# LB_BIT_1IN_2OUT-XL-v03_1_1x.net
KiCad netlist of a schematic drawn in EAGLE
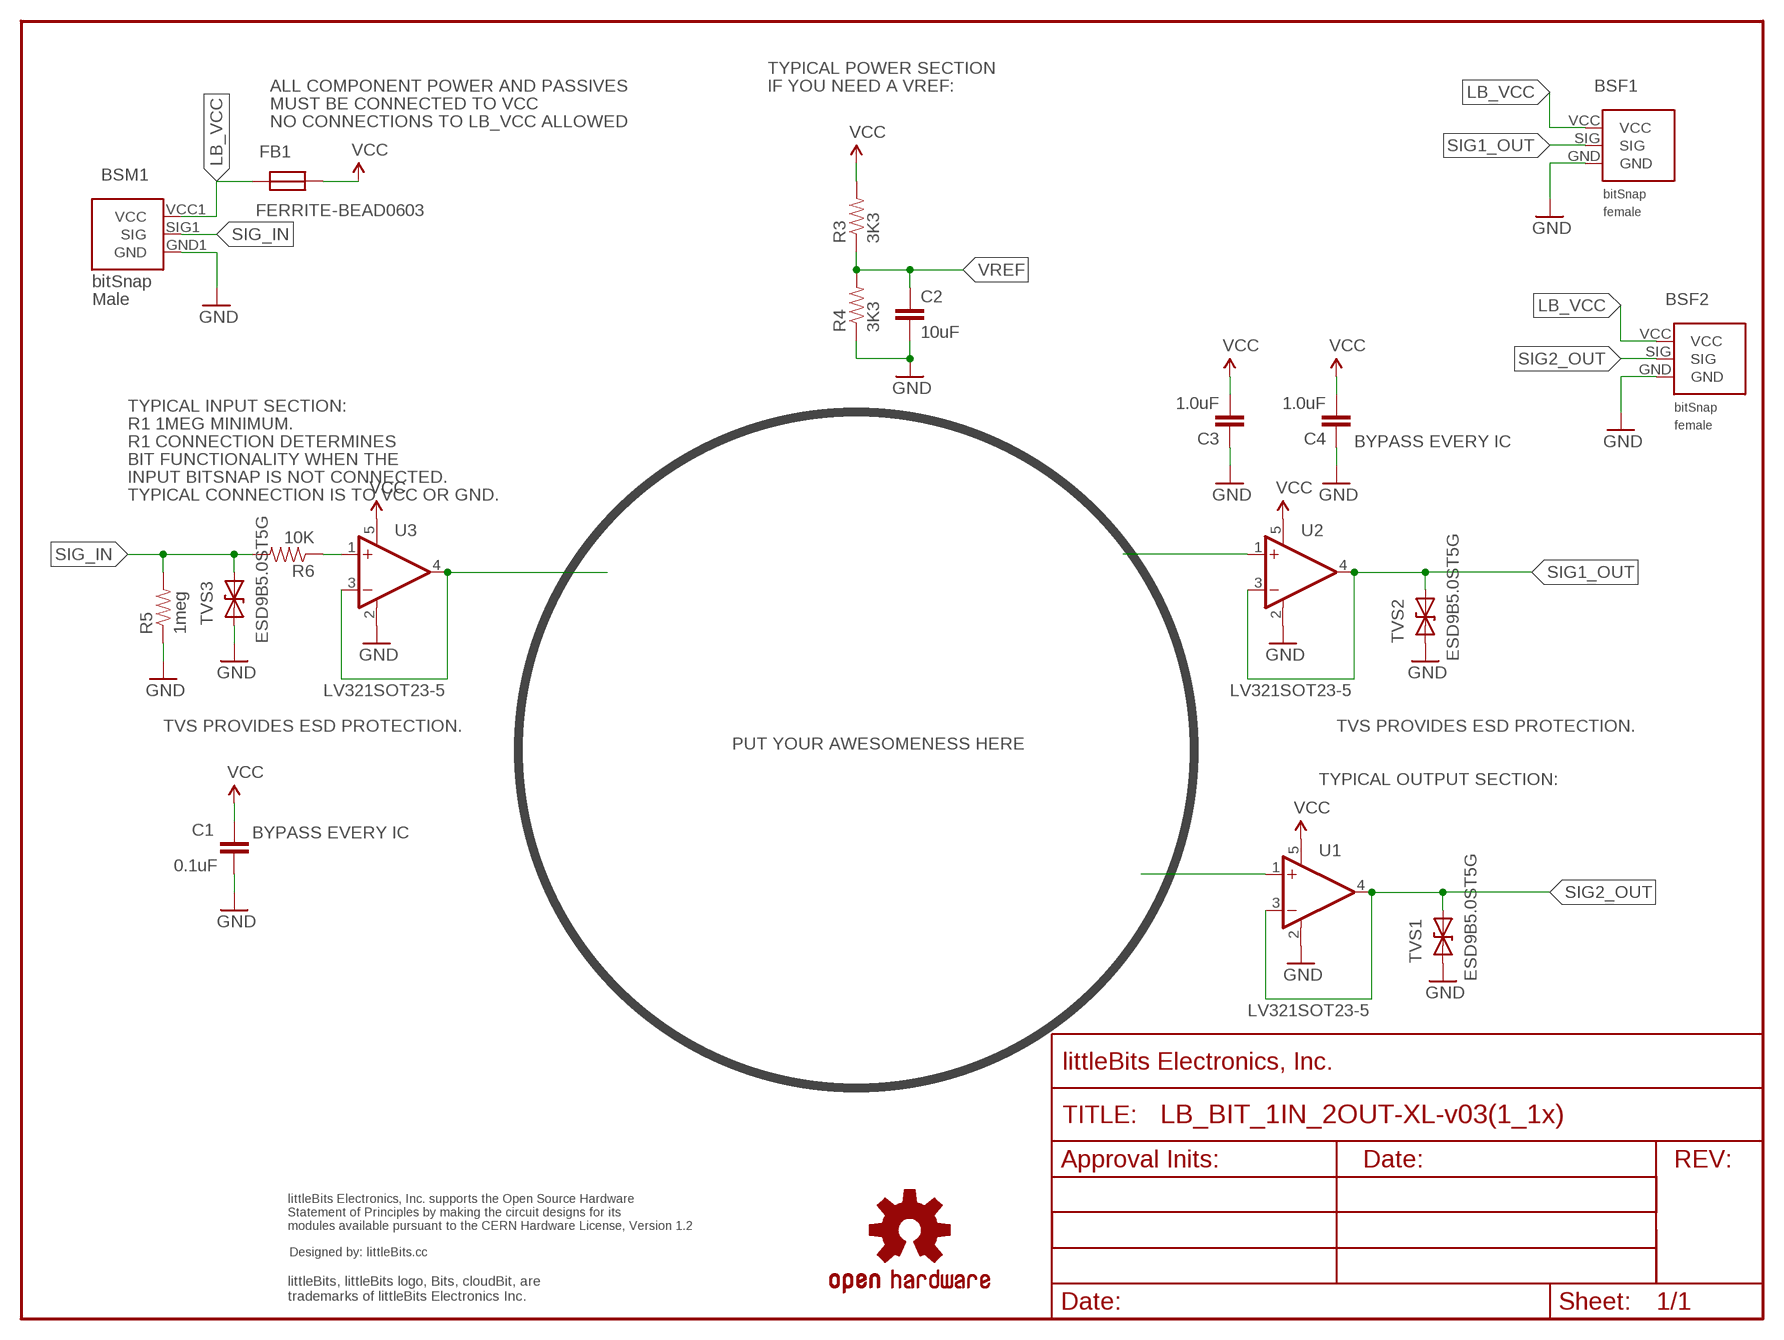
[diagram p0: schematic, sheet 1]

(export (version "E")
  (design (tool "Eeschema 10.0.6"))
  (components
    (comp (ref "BSF1")
      (value "BITSNAP_V03_FEMALE")
      (footprint "eagle-import:BITSNAP_V03_FEMALE")
      (libsource (lib "eagle-import") (part "BITSNAP_V03_FEMALE"))
    )
    (comp (ref "BSF2")
      (value "BITSNAP_V03_FEMALE")
      (footprint "eagle-import:BITSNAP_V03_FEMALE")
      (libsource (lib "eagle-import") (part "BITSNAP_V03_FEMALE"))
    )
    (comp (ref "BSM1")
      (value "BITSNAP_V03_MALE")
      (footprint "eagle-import:BITSNAP_V03_MALE")
      (libsource (lib "eagle-import") (part "BITSNAP_V03_MALE"))
    )
    (comp (ref "C1")
      (value "0.1uF")
      (footprint "eagle-import:CAP-0603")
      (libsource (lib "eagle-import") (part "CAPCAP-0603"))
    )
    (comp (ref "C2")
      (value "10uF")
      (footprint "eagle-import:CAP-0603")
      (libsource (lib "eagle-import") (part "CAPCAP-0603"))
    )
    (comp (ref "C3")
      (value "1.0uF")
      (footprint "eagle-import:CAP-0603")
      (libsource (lib "eagle-import") (part "CAPCAP-0603"))
    )
    (comp (ref "C4")
      (value "1.0uF")
      (footprint "eagle-import:CAP-0603")
      (libsource (lib "eagle-import") (part "CAPCAP-0603"))
    )
    (comp (ref "FB1")
      (value "FERRITE-BEAD0603")
      (footprint "eagle-import:R0603")
      (libsource (lib "eagle-import") (part "FERRITE-BEAD0603"))
    )
    (comp (ref "FRAME1")
      (value "FRAME-LETTER")
      (footprint "eagle-import:FABDWG01-OHW")
      (libsource (lib "eagle-import") (part "FRAME-LETTER"))
    )
    (comp (ref "R3")
      (value "3K3")
      (footprint "eagle-import:RES-0603")
      (libsource (lib "eagle-import") (part "RESISTOR0603"))
    )
    (comp (ref "R4")
      (value "3K3")
      (footprint "eagle-import:RES-0603")
      (libsource (lib "eagle-import") (part "RESISTOR0603"))
    )
    (comp (ref "R5")
      (value "1meg")
      (footprint "eagle-import:RES-0603")
      (libsource (lib "eagle-import") (part "RESISTOR0603"))
    )
    (comp (ref "R6")
      (value "10K")
      (footprint "eagle-import:RES-0603")
      (libsource (lib "eagle-import") (part "RESISTOR0603"))
    )
    (comp (ref "TVS1")
      (value "ESD9B5.0ST5G")
      (footprint "eagle-import:SOD-923")
      (libsource (lib "eagle-import") (part "DIODE-TVSSOD-923"))
    )
    (comp (ref "TVS2")
      (value "ESD9B5.0ST5G")
      (footprint "eagle-import:SOD-923")
      (libsource (lib "eagle-import") (part "DIODE-TVSSOD-923"))
    )
    (comp (ref "TVS3")
      (value "ESD9B5.0ST5G")
      (footprint "eagle-import:SOD-923")
      (libsource (lib "eagle-import") (part "DIODE-TVSSOD-923"))
    )
    (comp (ref "U$1")
      (value "OSHW-LOGOL")
      (footprint "eagle-import:OSHW-LOGO-L")
      (libsource (lib "eagle-import") (part "OSHW-LOGOL"))
    )
    (comp (ref "U$2")
      (value "OSHWCREDIT")
      (footprint "eagle-import:OSHWCREDIT")
      (libsource (lib "eagle-import") (part "OSHWCREDIT"))
    )
    (comp (ref "U1")
      (value "LV321SOT23-5")
      (footprint "eagle-import:SOT23-5")
      (libsource (lib "eagle-import") (part "LV321SOT23-5"))
    )
    (comp (ref "U2")
      (value "LV321SOT23-5")
      (footprint "eagle-import:SOT23-5")
      (libsource (lib "eagle-import") (part "LV321SOT23-5"))
    )
    (comp (ref "U3")
      (value "LV321SOT23-5")
      (footprint "eagle-import:SOT23-5")
      (libsource (lib "eagle-import") (part "LV321SOT23-5"))
    )
  )
  (nets
    (net (code "1") (name "GND") (class "Default")
      (node (ref "BSF1") (pin "GND") (pinfunction "GND_GND") (pintype "bidirectional"))
      (node (ref "BSF2") (pin "GND") (pinfunction "GND_GND") (pintype "bidirectional"))
      (node (ref "BSM1") (pin "GND1") (pinfunction "GND_GND1") (pintype "bidirectional"))
      (node (ref "C1") (pin "2") (pinfunction "2_2") (pintype "passive"))
      (node (ref "C2") (pin "2") (pinfunction "2_2") (pintype "passive"))
      (node (ref "C3") (pin "1") (pinfunction "1_1") (pintype "passive"))
      (node (ref "C4") (pin "1") (pinfunction "1_1") (pintype "passive"))
      (node (ref "R4") (pin "1") (pinfunction "1_1") (pintype "passive"))
      (node (ref "R5") (pin "1") (pinfunction "1_1") (pintype "passive"))
      (node (ref "TVS1") (pin "1") (pinfunction "A_1") (pintype "passive"))
      (node (ref "TVS2") (pin "1") (pinfunction "A_1") (pintype "passive"))
      (node (ref "TVS3") (pin "1") (pinfunction "A_1") (pintype "passive"))
      (node (ref "U1") (pin "2") (pinfunction "V-_2") (pintype "power_in"))
      (node (ref "U2") (pin "2") (pinfunction "V-_2") (pintype "power_in"))
      (node (ref "U3") (pin "2") (pinfunction "V-_2") (pintype "power_in"))
    )
    (net (code "2") (name "LB_VCC") (class "Default")
      (node (ref "BSF1") (pin "VCC") (pinfunction "VCC_VCC") (pintype "bidirectional"))
      (node (ref "BSF2") (pin "VCC") (pinfunction "VCC_VCC") (pintype "bidirectional"))
      (node (ref "BSM1") (pin "VCC1") (pinfunction "VCC_VCC1") (pintype "bidirectional"))
      (node (ref "FB1") (pin "2") (pinfunction "P$2_2") (pintype "bidirectional"))
    )
    (net (code "3") (name "Net-(U3-+IN)") (class "Default")
      (node (ref "R6") (pin "1") (pinfunction "1_1") (pintype "passive"))
      (node (ref "U3") (pin "1") (pinfunction "+IN_1") (pintype "input"))
    )
    (net (code "4") (name "Net-(U3--IN)") (class "Default")
      (node (ref "U3") (pin "3") (pinfunction "-IN_3") (pintype "input"))
      (node (ref "U3") (pin "4") (pinfunction "OUT_4") (pintype "output"))
    )
    (net (code "5") (name "SIG1_OUT") (class "Default")
      (node (ref "BSF1") (pin "SIG") (pinfunction "SIG_SIG") (pintype "bidirectional"))
      (node (ref "TVS2") (pin "2") (pinfunction "C_2") (pintype "passive"))
      (node (ref "U2") (pin "3") (pinfunction "-IN_3") (pintype "input"))
      (node (ref "U2") (pin "4") (pinfunction "OUT_4") (pintype "output"))
    )
    (net (code "6") (name "SIG2_OUT") (class "Default")
      (node (ref "BSF2") (pin "SIG") (pinfunction "SIG_SIG") (pintype "bidirectional"))
      (node (ref "TVS1") (pin "2") (pinfunction "C_2") (pintype "passive"))
      (node (ref "U1") (pin "3") (pinfunction "-IN_3") (pintype "input"))
      (node (ref "U1") (pin "4") (pinfunction "OUT_4") (pintype "output"))
    )
    (net (code "7") (name "SIG_IN") (class "Default")
      (node (ref "BSM1") (pin "SIG1") (pinfunction "SIG_SIG1") (pintype "bidirectional"))
      (node (ref "R5") (pin "2") (pinfunction "2_2") (pintype "passive"))
      (node (ref "R6") (pin "2") (pinfunction "2_2") (pintype "passive"))
      (node (ref "TVS3") (pin "2") (pinfunction "C_2") (pintype "passive"))
    )
    (net (code "8") (name "VCC") (class "Default")
      (node (ref "C1") (pin "1") (pinfunction "1_1") (pintype "passive"))
      (node (ref "C3") (pin "2") (pinfunction "2_2") (pintype "passive"))
      (node (ref "C4") (pin "2") (pinfunction "2_2") (pintype "passive"))
      (node (ref "FB1") (pin "1") (pinfunction "P$1_1") (pintype "bidirectional"))
      (node (ref "R3") (pin "2") (pinfunction "2_2") (pintype "passive"))
      (node (ref "U1") (pin "5") (pinfunction "V+_5") (pintype "power_in"))
      (node (ref "U2") (pin "5") (pinfunction "V+_5") (pintype "power_in"))
      (node (ref "U3") (pin "5") (pinfunction "V+_5") (pintype "power_in"))
    )
    (net (code "9") (name "VREF") (class "Default")
      (node (ref "C2") (pin "1") (pinfunction "1_1") (pintype "passive"))
      (node (ref "R3") (pin "1") (pinfunction "1_1") (pintype "passive"))
      (node (ref "R4") (pin "2") (pinfunction "2_2") (pintype "passive"))
    )
    (net (code "10") (name "unconnected-(U1-+IN-Pad1)") (class "Default")
      (node (ref "U1") (pin "1") (pinfunction "+IN_1") (pintype "input"))
    )
    (net (code "11") (name "unconnected-(U2-+IN-Pad1)") (class "Default")
      (node (ref "U2") (pin "1") (pinfunction "+IN_1") (pintype "input"))
    )
  )
)
